# design.net
KiCad netlist of a schematic drawn in EAGLE
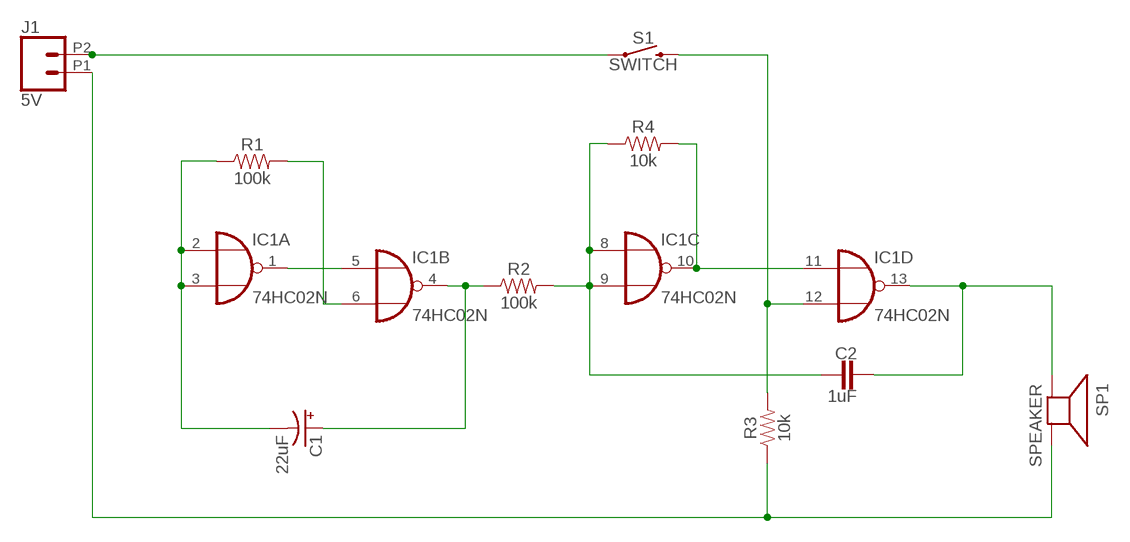
[diagram p0: schematic, sheet 1]

(export (version "E")
  (design (tool "Eeschema 10.0.6"))
  (components
    (comp (ref "C1")
      (value "22uF")
      (footprint "eagle-import:CPOL-RADIAL-2.5MM-5MM")
      (libsource (lib "eagle-import") (part "10UF-POLAR-RADIAL-2.5MM-25V-20%"))
    )
    (comp (ref "C2")
      (value "1uF")
      (footprint "eagle-import:CAP-PTH-SMALL-KIT")
      (libsource (lib "eagle-import") (part "0.1UF-KIT-EZ-50V-20%"))
    )
    (comp (ref "IC1")
      (value "74HC02N")
      (footprint "eagle-import:DIL14")
      (libsource (lib "eagle-import") (part "7402NHC"))
    )
    (comp (ref "J1")
      (value "5V")
      (footprint "eagle-import:1X02_2.54_SCREWTERM")
      (libsource (lib "eagle-import") (part "CONN_022.54MM_SCREWTERM"))
    )
    (comp (ref "R1")
      (value "100k")
      (footprint "eagle-import:AXIAL-0.3")
      (libsource (lib "eagle-import") (part "10KOHM-HORIZ-1/4W-5%"))
    )
    (comp (ref "R2")
      (value "100k")
      (footprint "eagle-import:AXIAL-0.3")
      (libsource (lib "eagle-import") (part "10KOHM-HORIZ-1/4W-5%"))
    )
    (comp (ref "R3")
      (value "10k")
      (footprint "eagle-import:AXIAL-0.3")
      (libsource (lib "eagle-import") (part "10KOHM-HORIZ-1/4W-5%"))
    )
    (comp (ref "R4")
      (value "10k")
      (footprint "eagle-import:AXIAL-0.3")
      (libsource (lib "eagle-import") (part "10KOHM-HORIZ-1/4W-5%"))
    )
    (comp (ref "S1")
      (value "SWITCH")
      (footprint "eagle-import:TACTILE_SWITCH_PTH_6.0MM")
      (libsource (lib "eagle-import") (part "MOMENTARY-SWITCH-SPST-PTH-6.0MM"))
    )
    (comp (ref "SP1")
      (value "SPEAKER")
      (footprint "eagle-import:PS12")
      (libsource (lib "eagle-import") (part "SPEAKER/PS12"))
    )
  )
  (nets
    (net (code "1") (name "Net-(C1-+)") (class "Default")
      (node (ref "C1") (pin "1") (pinfunction "+_1") (pintype "passive"))
      (node (ref "IC1") (pin "4") (pinfunction "O_4") (pintype "output"))
      (node (ref "R2") (pin "P$1") (pinfunction "1_P$1") (pintype "passive"))
    )
    (net (code "2") (name "Net-(C1--)") (class "Default")
      (node (ref "C1") (pin "2") (pinfunction "-_2") (pintype "passive"))
      (node (ref "IC1") (pin "2") (pinfunction "I0_2") (pintype "input"))
      (node (ref "IC1") (pin "3") (pinfunction "I1_3") (pintype "input"))
      (node (ref "R1") (pin "P$1") (pinfunction "1_P$1") (pintype "passive"))
    )
    (net (code "3") (name "Net-(IC1A-O)") (class "Default")
      (node (ref "IC1") (pin "1") (pinfunction "O_1") (pintype "output"))
      (node (ref "IC1") (pin "5") (pinfunction "I0_5") (pintype "input"))
    )
    (net (code "4") (name "Net-(IC1B-I1)") (class "Default")
      (node (ref "IC1") (pin "6") (pinfunction "I1_6") (pintype "input"))
      (node (ref "R1") (pin "P$2") (pinfunction "2_P$2") (pintype "passive"))
    )
    (net (code "5") (name "Net-(IC1C-I0)") (class "Default")
      (node (ref "C2") (pin "2") (pinfunction "2_2") (pintype "passive"))
      (node (ref "IC1") (pin "8") (pinfunction "I0_8") (pintype "input"))
      (node (ref "IC1") (pin "9") (pinfunction "I1_9") (pintype "input"))
      (node (ref "R2") (pin "P$2") (pinfunction "2_P$2") (pintype "passive"))
      (node (ref "R4") (pin "P$1") (pinfunction "1_P$1") (pintype "passive"))
    )
    (net (code "6") (name "Net-(IC1C-O)") (class "Default")
      (node (ref "IC1") (pin "10") (pinfunction "O_10") (pintype "output"))
      (node (ref "IC1") (pin "11") (pinfunction "I0_11") (pintype "input"))
      (node (ref "R4") (pin "P$2") (pinfunction "2_P$2") (pintype "passive"))
    )
    (net (code "7") (name "Net-(IC1D-I1)") (class "Default")
      (node (ref "IC1") (pin "12") (pinfunction "I1_12") (pintype "input"))
      (node (ref "R3") (pin "P$2") (pinfunction "2_P$2") (pintype "passive"))
      (node (ref "S1") (pin "3") (pinfunction "2_3") (pintype "passive"))
    )
    (net (code "8") (name "Net-(IC1D-O)") (class "Default")
      (node (ref "C2") (pin "1") (pinfunction "1_1") (pintype "passive"))
      (node (ref "IC1") (pin "13") (pinfunction "O_13") (pintype "output"))
      (node (ref "SP1") (pin "P$1") (pinfunction "+_P$1") (pintype "passive"))
    )
    (net (code "9") (name "Net-(J1-1)") (class "Default")
      (node (ref "J1") (pin "P1") (pinfunction "1_P1") (pintype "passive"))
      (node (ref "R3") (pin "P$1") (pinfunction "1_P$1") (pintype "passive"))
      (node (ref "SP1") (pin "P$2") (pinfunction "-_P$2") (pintype "passive"))
    )
    (net (code "10") (name "Net-(J1-2)") (class "Default")
      (node (ref "J1") (pin "P2") (pinfunction "2_P2") (pintype "passive"))
      (node (ref "S1") (pin "1") (pinfunction "1_1") (pintype "passive"))
    )
  )
)
